# FC_main.net
KiCad netlist of a schematic drawn in Altium Designer
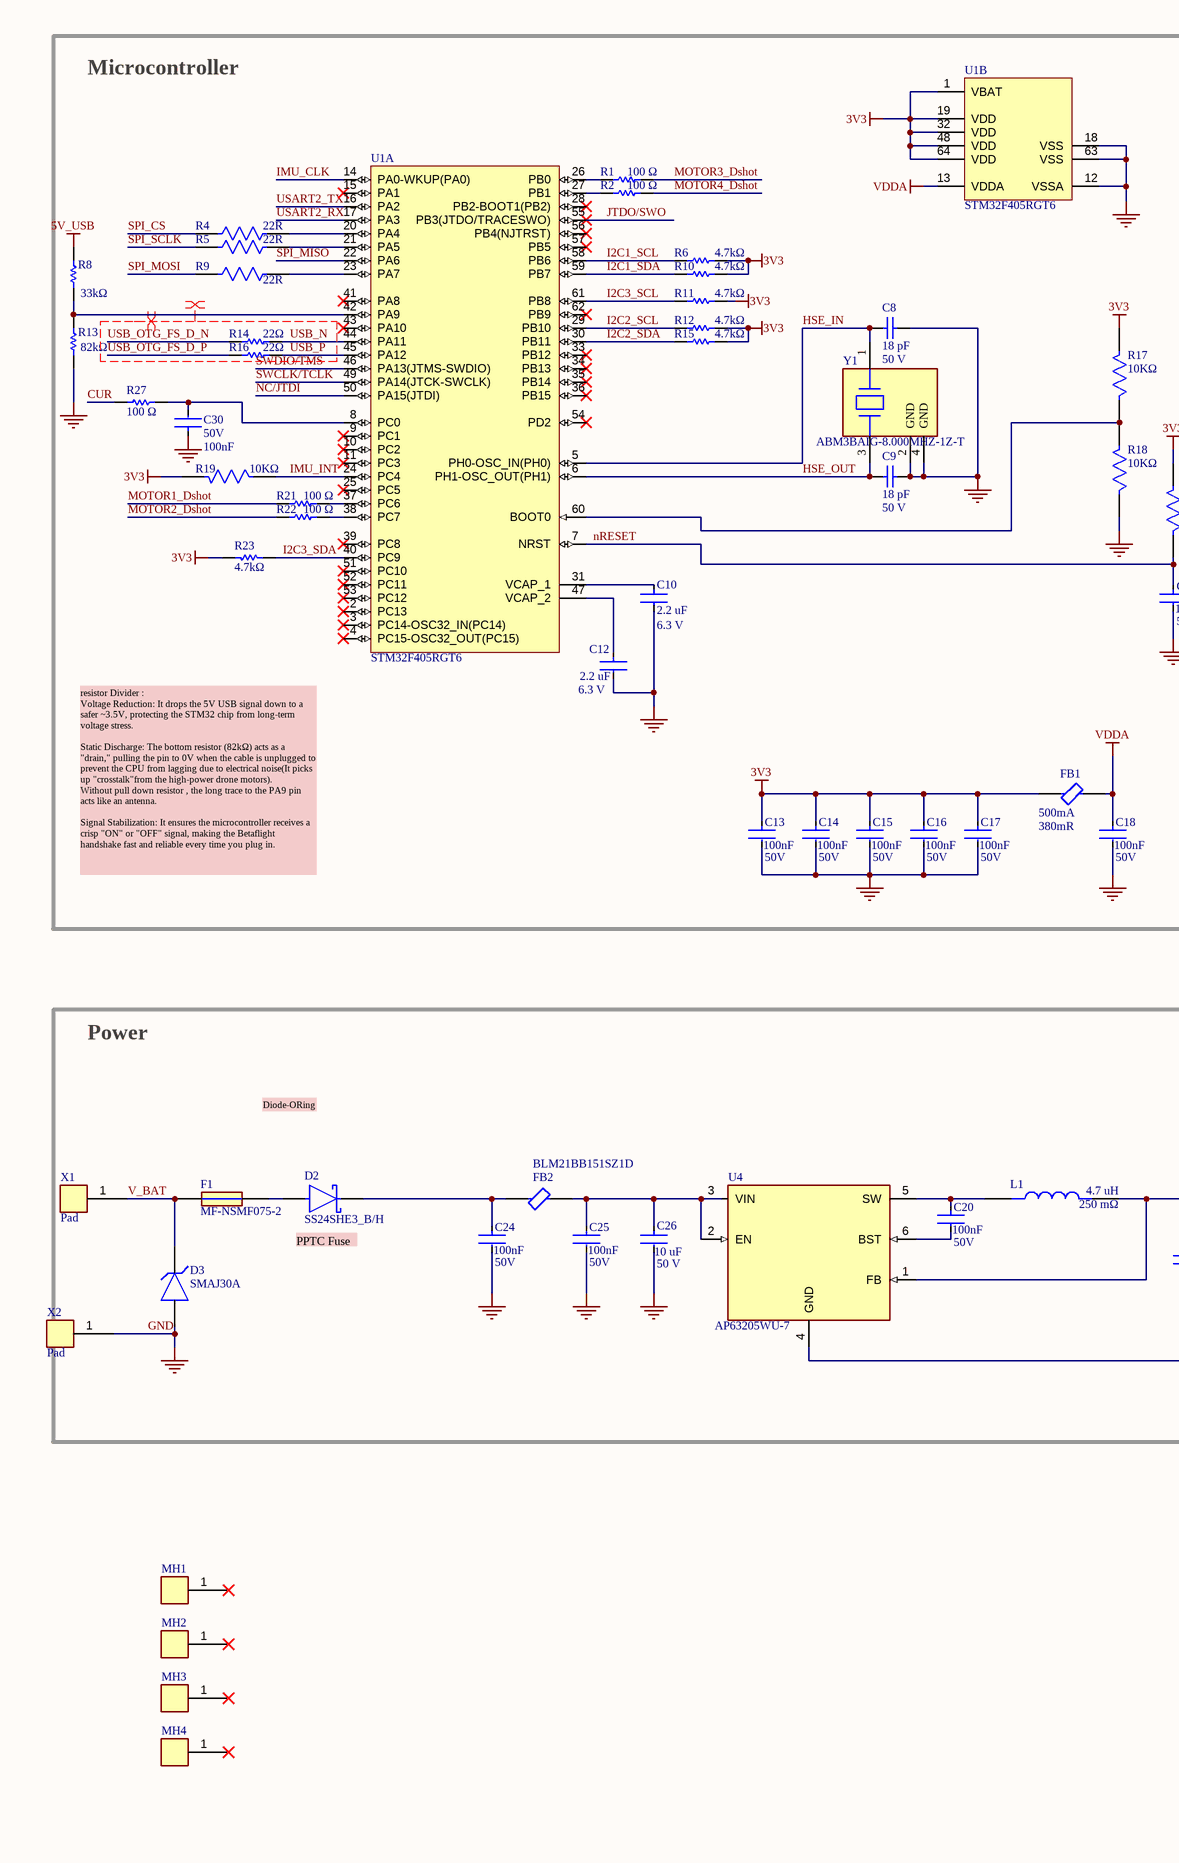
[diagram p0: FC_main.SchDoc, left]
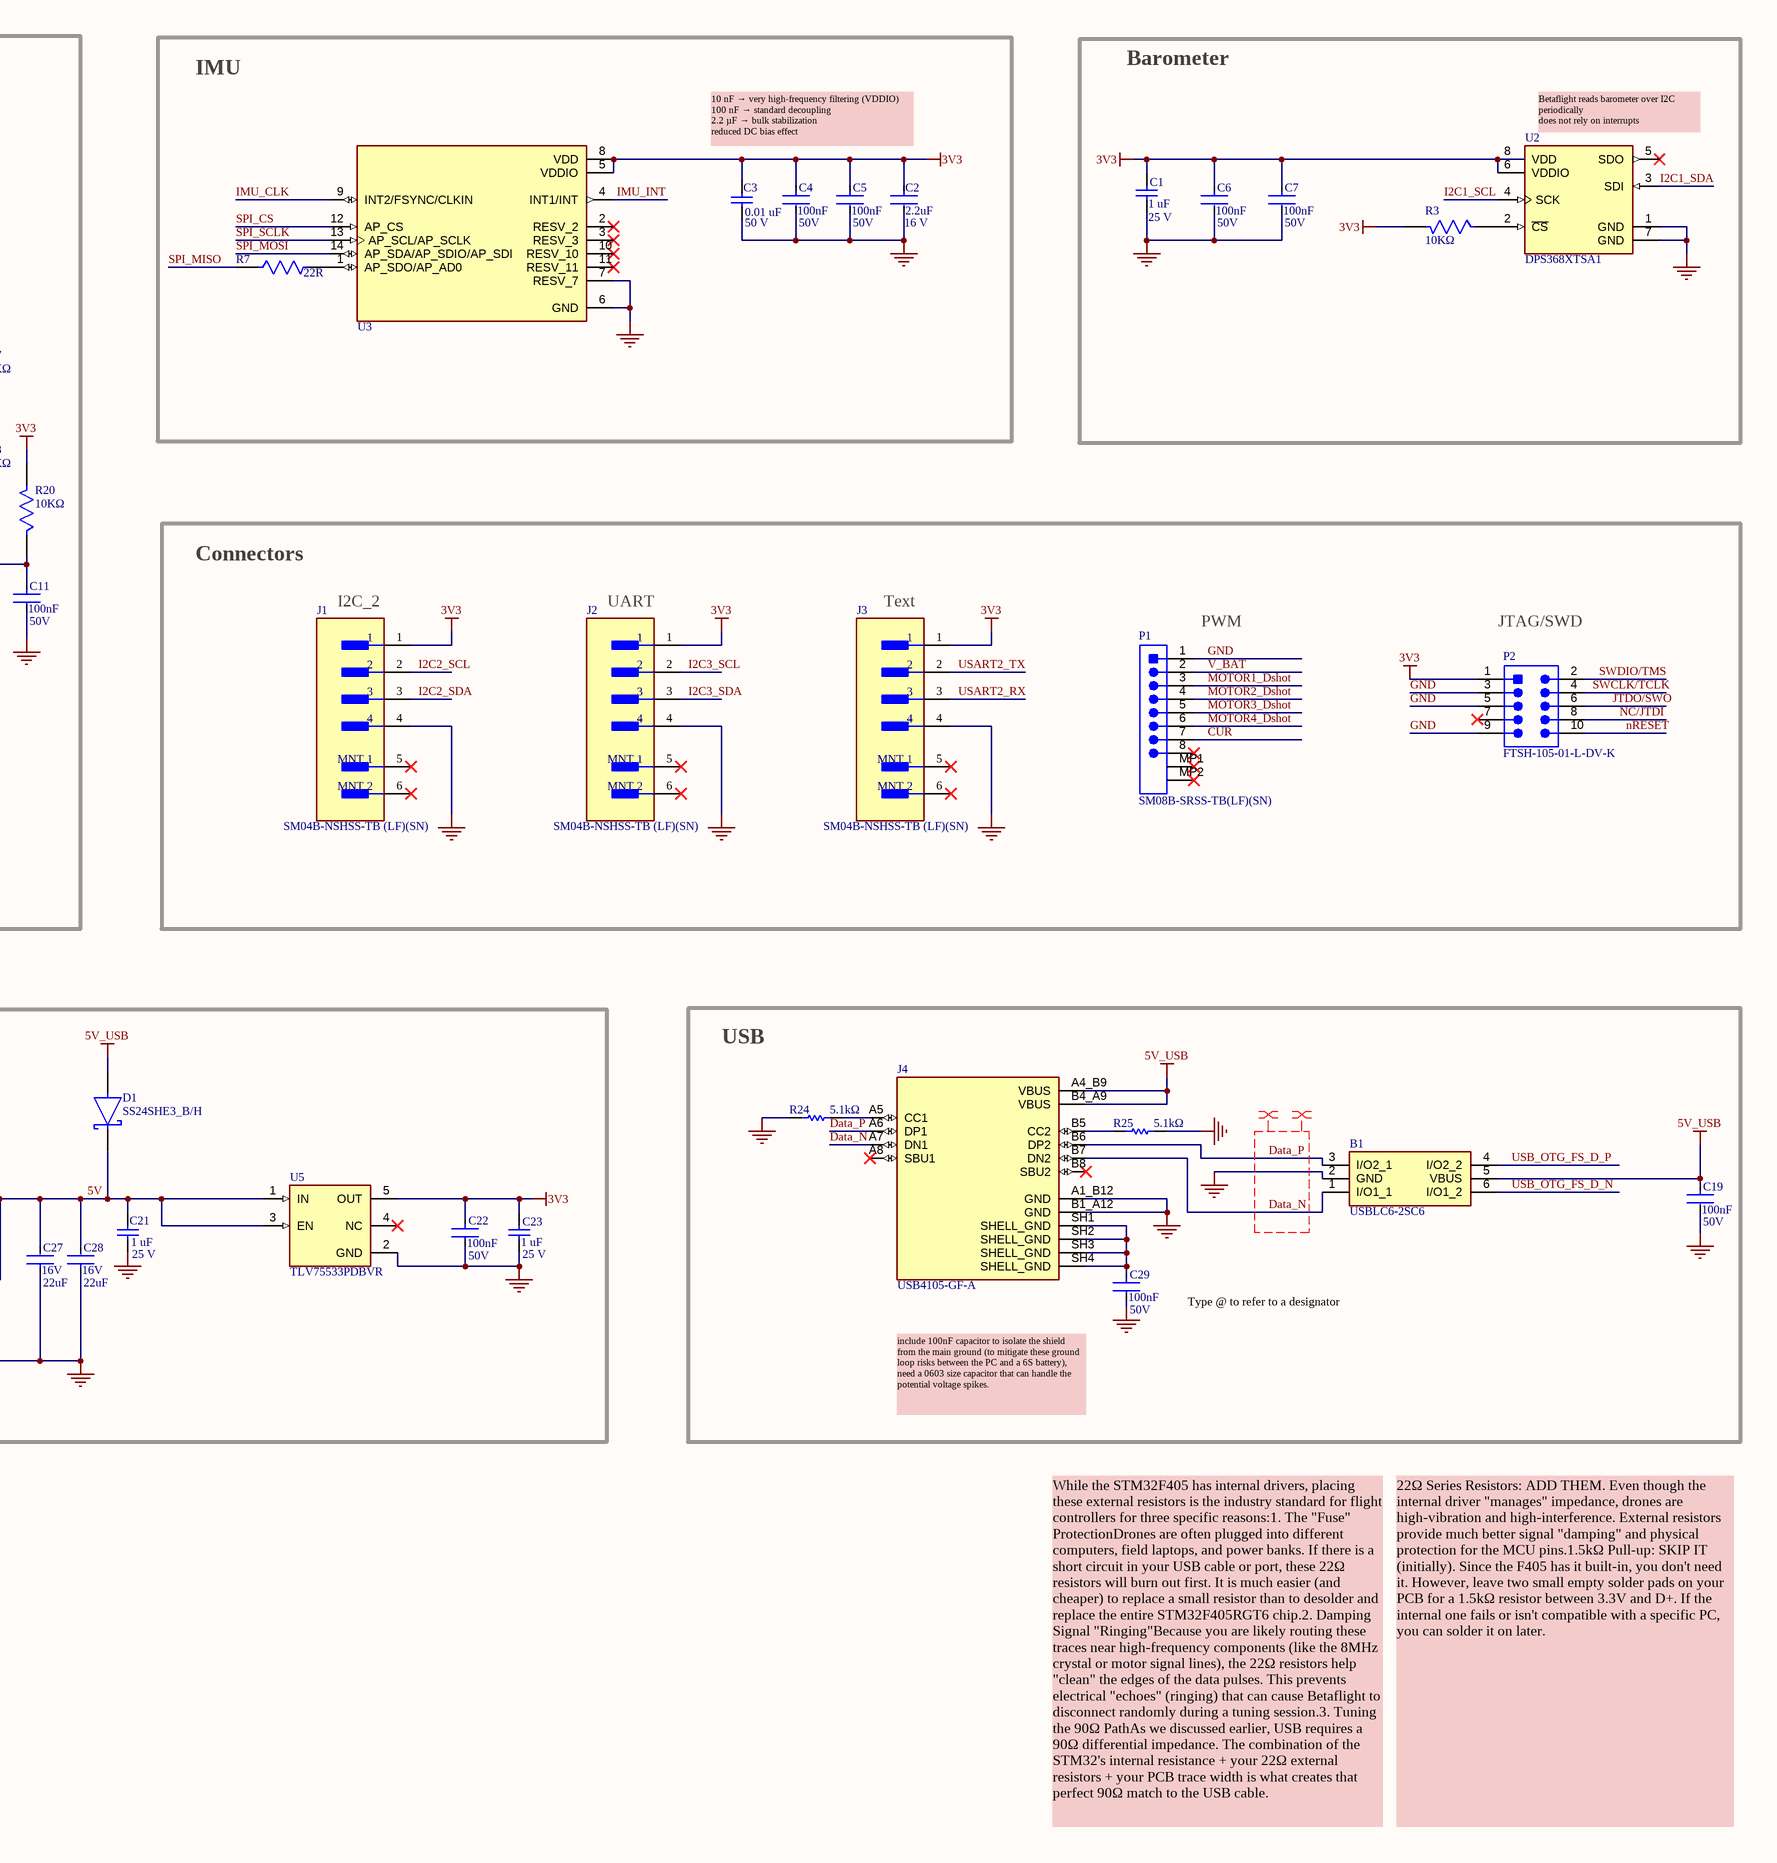
[diagram p1: FC_main.SchDoc, right]

(export (version "E")
  (design (tool "Eeschema 10.0.6"))
  (components
    (comp (ref "B1")
      (value "USBLC6-2SC6")
      (footprint "SOT95P280X145-6N")
      (description "TVS Diode Array Uni-Directional USBLC6-2SC6 17V, SOT-23 6-Pin")
      (fields (field (name "MOUSER PART NUMBER") "511-USBLC6-2SC6"))
      (libsource (lib "USBLC6-2SC6") (part "USBLC6-2SC6"))
    )
    (comp (ref "C1")
      (value "GRM188R71E105KA12D")
      (footprint "CAPC1608X90X35ML10T15")
      (fields
        (field (name "MANUFACTURER") "Murata")
        (field (name "CAPACITANCE") "1 uF")
        (field (name "RATED DC VOLTAGE") "25 V")
      )
      (libsource (lib "Altium Content Vault") (part "CAP"))
    )
    (comp (ref "C2")
      (value "GRM188Z71C225KE43D")
      (footprint "FP-GRM188-0_2-MFG")
      (description "Chip Multilayer Ceramic Capacitors for General Purpose, 0603, 2.2uF, X7R, 15%, 10%, 16V")
      (fields (field (name "CAPACITANCE") "2.2uF") (field (name "RATED VOLTAGE DC") "16 V"))
      (libsource (lib "Altium Content Vault") (part "11868f565c42a9108669ba33697ecf6"))
    )
    (comp (ref "C3")
      (value "GCM188R71H103KA37J")
      (footprint "CAPC1608X90X35NL10T15")
      (fields
        (field (name "MANUFACTURER") "Murata")
        (field (name "CAPACITANCE") "0.01 uF")
        (field (name "RATED DC VOLTAGE") "50 V")
      )
      (libsource (lib "Altium Content Vault") (part "CAP"))
    )
    (comp (ref "C4")
      (value "CGA3E2X7R1H104K080AA")
      (footprint "FP-CGA3E-0_3-0_1-IPC_A")
      (description "Cap Ceramic 100nF 50V X7R 10% Pad SMD 0603 +125°C Automotive T/R")
      (fields
        (field (name "TOLERANCE") "10%")
        (field (name "VOLTAGE RATING") "50V")
        (field (name "CAPACITANCE") "100nF")
        (field (name "VOLTAGE") "50V")
      )
      (libsource (lib "Altium Content Vault") (part "b4654b650e69147ec39a6b967a45e02"))
    )
    (comp (ref "C5")
      (value "CGA3E2X7R1H104K080AA")
      (footprint "FP-CGA3E-0_3-0_1-IPC_A")
      (description "Cap Ceramic 100nF 50V X7R 10% Pad SMD 0603 +125°C Automotive T/R")
      (fields
        (field (name "TOLERANCE") "10%")
        (field (name "VOLTAGE RATING") "50V")
        (field (name "CAPACITANCE") "100nF")
        (field (name "VOLTAGE") "50V")
      )
      (libsource (lib "Altium Content Vault") (part "b4654b650e69147ec39a6b967a45e02"))
    )
    (comp (ref "C6")
      (value "CGA3E2X7R1H104K080AA")
      (footprint "FP-CGA3E-0_3-0_1-IPC_A")
      (description "Cap Ceramic 100nF 50V X7R 10% Pad SMD 0603 +125°C Automotive T/R")
      (fields
        (field (name "TOLERANCE") "10%")
        (field (name "VOLTAGE RATING") "50V")
        (field (name "CAPACITANCE") "100nF")
        (field (name "VOLTAGE") "50V")
      )
      (libsource (lib "Altium Content Vault") (part "b4654b650e69147ec39a6b967a45e02"))
    )
    (comp (ref "C7")
      (value "CGA3E2X7R1H104K080AA")
      (footprint "FP-CGA3E-0_3-0_1-IPC_A")
      (description "Cap Ceramic 100nF 50V X7R 10% Pad SMD 0603 +125°C Automotive T/R")
      (fields
        (field (name "TOLERANCE") "10%")
        (field (name "VOLTAGE RATING") "50V")
        (field (name "CAPACITANCE") "100nF")
        (field (name "VOLTAGE") "50V")
      )
      (libsource (lib "Altium Content Vault") (part "b4654b650e69147ec39a6b967a45e02"))
    )
    (comp (ref "C8")
      (value "GRM1555C1H180JA01D")
      (footprint "CAPC1005X55X25NL05T10")
      (fields
        (field (name "MANUFACTURER") "Murata")
        (field (name "CAPACITANCE") "18 pF")
        (field (name "RATED DC VOLTAGE") "50 V")
      )
      (libsource (lib "Altium Content Vault") (part "CAP"))
    )
    (comp (ref "C9")
      (value "GRM1555C1H180JA01D")
      (footprint "CAPC1005X55X25NL05T10")
      (fields
        (field (name "MANUFACTURER") "Murata")
        (field (name "CAPACITANCE") "18 pF")
        (field (name "RATED DC VOLTAGE") "50 V")
      )
      (libsource (lib "Altium Content Vault") (part "CAP"))
    )
    (comp (ref "C10")
      (value "CC0603KRX7R5BB225")
      (footprint "FP-CC0603-DA-MFG")
      (description "0603 2.2 uF 6.3 V 10% Tolerance X7R Multilayer Ceramic Capacitor")
      (fields
        (field (name "VOLTAGE") "6.3 V")
        (field (name "OCTOPART") "https://octopart.com/cc0603krx7r5bb225-yageo-25629540")
        (field (name "CAPACITANCE") "2.2 uF")
        (field (name "MANUFACTURER") "YAGEO")
      )
      (libsource (lib "Altium Content Vault") (part "11868f565c42a9108669ba33697ecf6"))
    )
    (comp (ref "C11")
      (value "CGA3E2X7R1H104K080AA")
      (footprint "FP-CGA3E-0_3-0_1-IPC_A")
      (description "Cap Ceramic 100nF 50V X7R 10% Pad SMD 0603 +125°C Automotive T/R")
      (fields
        (field (name "TOLERANCE") "10%")
        (field (name "VOLTAGE RATING") "50V")
        (field (name "CAPACITANCE") "100nF")
        (field (name "VOLTAGE") "50V")
      )
      (libsource (lib "Altium Content Vault") (part "b4654b650e69147ec39a6b967a45e02"))
    )
    (comp (ref "C12")
      (value "CC0603KRX7R5BB225")
      (footprint "FP-CC0603-DA-MFG")
      (description "0603 2.2 uF 6.3 V 10% Tolerance X7R Multilayer Ceramic Capacitor")
      (fields
        (field (name "VOLTAGE") "6.3 V")
        (field (name "OCTOPART") "https://octopart.com/cc0603krx7r5bb225-yageo-25629540")
        (field (name "CAPACITANCE") "2.2 uF")
        (field (name "MANUFACTURER") "YAGEO")
      )
      (libsource (lib "Altium Content Vault") (part "11868f565c42a9108669ba33697ecf6"))
    )
    (comp (ref "C13")
      (value "CGA3E2X7R1H104K080AA")
      (footprint "FP-CGA3E-0_3-0_1-IPC_A")
      (description "Cap Ceramic 100nF 50V X7R 10% Pad SMD 0603 +125°C Automotive T/R")
      (fields
        (field (name "TOLERANCE") "10%")
        (field (name "VOLTAGE RATING") "50V")
        (field (name "CAPACITANCE") "100nF")
        (field (name "VOLTAGE") "50V")
      )
      (libsource (lib "Altium Content Vault") (part "b4654b650e69147ec39a6b967a45e02"))
    )
    (comp (ref "C14")
      (value "CGA3E2X7R1H104K080AA")
      (footprint "FP-CGA3E-0_3-0_1-IPC_A")
      (description "Cap Ceramic 100nF 50V X7R 10% Pad SMD 0603 +125°C Automotive T/R")
      (fields
        (field (name "TOLERANCE") "10%")
        (field (name "VOLTAGE RATING") "50V")
        (field (name "CAPACITANCE") "100nF")
        (field (name "VOLTAGE") "50V")
      )
      (libsource (lib "Altium Content Vault") (part "b4654b650e69147ec39a6b967a45e02"))
    )
    (comp (ref "C15")
      (value "CGA3E2X7R1H104K080AA")
      (footprint "FP-CGA3E-0_3-0_1-IPC_A")
      (description "Cap Ceramic 100nF 50V X7R 10% Pad SMD 0603 +125°C Automotive T/R")
      (fields
        (field (name "TOLERANCE") "10%")
        (field (name "VOLTAGE RATING") "50V")
        (field (name "CAPACITANCE") "100nF")
        (field (name "VOLTAGE") "50V")
      )
      (libsource (lib "Altium Content Vault") (part "b4654b650e69147ec39a6b967a45e02"))
    )
    (comp (ref "C16")
      (value "CGA3E2X7R1H104K080AA")
      (footprint "FP-CGA3E-0_3-0_1-IPC_A")
      (description "Cap Ceramic 100nF 50V X7R 10% Pad SMD 0603 +125°C Automotive T/R")
      (fields
        (field (name "TOLERANCE") "10%")
        (field (name "VOLTAGE RATING") "50V")
        (field (name "CAPACITANCE") "100nF")
        (field (name "VOLTAGE") "50V")
      )
      (libsource (lib "Altium Content Vault") (part "b4654b650e69147ec39a6b967a45e02"))
    )
    (comp (ref "C17")
      (value "CGA3E2X7R1H104K080AA")
      (footprint "FP-CGA3E-0_3-0_1-IPC_A")
      (description "Cap Ceramic 100nF 50V X7R 10% Pad SMD 0603 +125°C Automotive T/R")
      (fields
        (field (name "TOLERANCE") "10%")
        (field (name "VOLTAGE RATING") "50V")
        (field (name "CAPACITANCE") "100nF")
        (field (name "VOLTAGE") "50V")
      )
      (libsource (lib "Altium Content Vault") (part "b4654b650e69147ec39a6b967a45e02"))
    )
    (comp (ref "C18")
      (value "CGA3E2X7R1H104K080AA")
      (footprint "FP-CGA3E-0_3-0_1-IPC_A")
      (description "Cap Ceramic 100nF 50V X7R 10% Pad SMD 0603 +125°C Automotive T/R")
      (fields
        (field (name "TOLERANCE") "10%")
        (field (name "VOLTAGE RATING") "50V")
        (field (name "CAPACITANCE") "100nF")
        (field (name "VOLTAGE") "50V")
      )
      (libsource (lib "Altium Content Vault") (part "b4654b650e69147ec39a6b967a45e02"))
    )
    (comp (ref "C19")
      (value "CGA3E2X7R1H104K080AA")
      (footprint "FP-CGA3E-0_3-0_1-IPC_A")
      (description "Cap Ceramic 100nF 50V X7R 10% Pad SMD 0603 +125°C Automotive T/R")
      (fields
        (field (name "TOLERANCE") "10%")
        (field (name "VOLTAGE RATING") "50V")
        (field (name "CAPACITANCE") "100nF")
        (field (name "VOLTAGE") "50V")
      )
      (libsource (lib "Altium Content Vault") (part "b4654b650e69147ec39a6b967a45e02"))
    )
    (comp (ref "C20")
      (value "CGA3E2X7R1H104K080AA")
      (footprint "FP-CGA3E-0_3-0_1-IPC_A")
      (description "Cap Ceramic 100nF 50V X7R 10% Pad SMD 0603 +125°C Automotive T/R")
      (fields
        (field (name "TOLERANCE") "10%")
        (field (name "VOLTAGE RATING") "50V")
        (field (name "CAPACITANCE") "100nF")
        (field (name "VOLTAGE") "50V")
      )
      (libsource (lib "Altium Content Vault") (part "b4654b650e69147ec39a6b967a45e02"))
    )
    (comp (ref "C21")
      (value "GRM188R71E105KA12D")
      (footprint "CAPC1608X90X35ML10T15")
      (fields
        (field (name "MANUFACTURER") "Murata")
        (field (name "CAPACITANCE") "1 uF")
        (field (name "RATED DC VOLTAGE") "25 V")
      )
      (libsource (lib "Altium Content Vault") (part "CAP"))
    )
    (comp (ref "C22")
      (value "CGA3E2X7R1H104K080AA")
      (footprint "FP-CGA3E-0_3-0_1-IPC_A")
      (description "Cap Ceramic 100nF 50V X7R 10% Pad SMD 0603 +125°C Automotive T/R")
      (fields
        (field (name "TOLERANCE") "10%")
        (field (name "VOLTAGE RATING") "50V")
        (field (name "CAPACITANCE") "100nF")
        (field (name "VOLTAGE") "50V")
      )
      (libsource (lib "Altium Content Vault") (part "b4654b650e69147ec39a6b967a45e02"))
    )
    (comp (ref "C23")
      (value "GRM188R71E105KA12D")
      (footprint "CAPC1608X90X35ML10T15")
      (fields
        (field (name "MANUFACTURER") "Murata")
        (field (name "CAPACITANCE") "1 uF")
        (field (name "RATED DC VOLTAGE") "25 V")
      )
      (libsource (lib "Altium Content Vault") (part "CAP"))
    )
    (comp (ref "C24")
      (value "CGA3E2X7R1H104K080AA")
      (footprint "FP-CGA3E-0_3-0_1-IPC_A")
      (description "Cap Ceramic 100nF 50V X7R 10% Pad SMD 0603 +125°C Automotive T/R")
      (fields
        (field (name "TOLERANCE") "10%")
        (field (name "VOLTAGE RATING") "50V")
        (field (name "CAPACITANCE") "100nF")
        (field (name "VOLTAGE") "50V")
      )
      (libsource (lib "Altium Content Vault") (part "b4654b650e69147ec39a6b967a45e02"))
    )
    (comp (ref "C25")
      (value "CGA3E2X7R1H104K080AA")
      (footprint "FP-CGA3E-0_3-0_1-IPC_A")
      (description "Cap Ceramic 100nF 50V X7R 10% Pad SMD 0603 +125°C Automotive T/R")
      (fields
        (field (name "TOLERANCE") "10%")
        (field (name "VOLTAGE RATING") "50V")
        (field (name "CAPACITANCE") "100nF")
        (field (name "VOLTAGE") "50V")
      )
      (libsource (lib "Altium Content Vault") (part "b4654b650e69147ec39a6b967a45e02"))
    )
    (comp (ref "C26")
      (value "C3216X7R1H106K160AC")
      (footprint "FP-C3216-160-0_3-MFG")
      (description "Multilayer Ceramic Capacitors 10uF ±10% 50V X7R SMD 1206")
      (fields (field (name "CAPACITANCE") "10 uF") (field (name "RATED DC VOLTAGE") "50 V"))
      (libsource (lib "Altium Content Vault") (part "02cd4be3c70576c341d710602a673aa"))
    )
    (comp (ref "C27")
      (value "C3225X7R1C226K250AC")
      (footprint "FP-C3225-250-0_4-IPC_C")
      (description "Multilayer Ceramic Capacitors 22uF ±10% 16V X7R SMD 1210")
      (fields
        (field (name "VOLTAGE RATING (DC)") "16V")
        (field (name "VOLTAGE") "16V")
        (field (name "TOLERANCE") "10%")
        (field (name "CAPACITANCE") "22uF")
      )
      (libsource (lib "Altium Content Vault") (part "02cd4be3c70576c341d710602a673aa"))
    )
    (comp (ref "C28")
      (value "C3225X7R1C226K250AC")
      (footprint "FP-C3225-250-0_4-IPC_C")
      (description "Multilayer Ceramic Capacitors 22uF ±10% 16V X7R SMD 1210")
      (fields
        (field (name "VOLTAGE RATING (DC)") "16V")
        (field (name "VOLTAGE") "16V")
        (field (name "TOLERANCE") "10%")
        (field (name "CAPACITANCE") "22uF")
      )
      (libsource (lib "Altium Content Vault") (part "02cd4be3c70576c341d710602a673aa"))
    )
    (comp (ref "C29")
      (value "CGA3E2X7R1H104K080AA")
      (footprint "FP-CGA3E-0_3-0_1-IPC_A")
      (description "Cap Ceramic 100nF 50V X7R 10% Pad SMD 0603 +125°C Automotive T/R")
      (fields
        (field (name "TOLERANCE") "10%")
        (field (name "VOLTAGE RATING") "50V")
        (field (name "CAPACITANCE") "100nF")
        (field (name "VOLTAGE") "50V")
      )
      (libsource (lib "Altium Content Vault") (part "b4654b650e69147ec39a6b967a45e02"))
    )
    (comp (ref "C30")
      (value "CGA3E2X7R1H104K080AA")
      (footprint "FP-CGA3E-0_3-0_1-IPC_A")
      (description "Cap Ceramic 100nF 50V X7R 10% Pad SMD 0603 +125°C Automotive T/R")
      (fields
        (field (name "TOLERANCE") "10%")
        (field (name "VOLTAGE RATING") "50V")
        (field (name "CAPACITANCE") "100nF")
        (field (name "VOLTAGE") "50V")
      )
      (libsource (lib "Altium Content Vault") (part "b4654b650e69147ec39a6b967a45e02"))
    )
    (comp (ref "D1")
      (value "SS24SHE3_B/H")
      (footprint "FP-95400-MFG")
      (description "DIODE SCHOTTKY 2A 40V DO-214AC")
      (libsource (lib "Altium Content Vault") (part "1d6ec82d83fb6aee721767c19dac4b9"))
    )
    (comp (ref "D2")
      (value "SS24SHE3_B/H")
      (footprint "FP-95400-MFG")
      (description "DIODE SCHOTTKY 2A 40V DO-214AC")
      (libsource (lib "Altium Content Vault") (part "1d6ec82d83fb6aee721767c19dac4b9"))
    )
    (comp (ref "D3")
      (value "SMAJ30A")
      (footprint "FP-SMA-MFG")
      (description "TVS DIODE 30V 48.4V SMA")
      (fields
        (field (name "OCTOPART") "https://octopart.com/smaj30a-bourns-12809375")
        (field (name "MANUFACTURER") "Bourns Inc.")
      )
      (libsource (lib "Altium Content Vault") (part "673ecd2ea4d7fb87b4005b0cb348b7d"))
    )
    (comp (ref "F1")
      (value "MF-NSMF075-2")
      (footprint "FUSC3216X70N")
      (description "Fuse, PTC, Resettable, SMD, 1206, 750mA Bourns 0.75A Surface Mount Resettable Fuse, 6 V")
      (fields (field (name "MOUSER PART NUMBER") "652-MF-NSMF075-2"))
      (libsource (lib "MF-NSMF075-2") (part "MF-NSMF075-2"))
    )
    (comp (ref "FB1")
      (value "BLM18AG601SN1D")
      (footprint "FP-BLM18-0_15-t0_8-MFG")
      (description "Chip Ferrite Bead, 0603, 600Ω @ 100MHz, 0.38Ω, 25%, 500mA")
      (fields
        (field (name "MAX DC CURRENT") "500mA")
        (field (name "DC RESISTANCE (DCR)") "380mR")
        (field (name "TOLERANCE") "25%")
      )
      (libsource (lib "Altium Content Vault") (part "5f30dd21d616792df468990f7003faa"))
    )
    (comp (ref "FB2")
      (value "BLM21BB151SZ1D")
      (footprint "FP-BLM21-0_2-t0_85-e0_5-IPC_B")
      (description "Chip Ferrite Bead, 0805, 150Ω @ 100MHz, 0.21Ω, 25%, 600mA")
      (libsource (lib "Altium Content Vault") (part "5f30dd21d616792df468990f7003faa"))
    )
    (comp (ref "J1")
      (value "SM04B-NSHSS-TB (LF)(SN)")
      (footprint "FP-SM04B-NSHSS-TB_LF_SN-MFG")
      (description "CONN HEADER SMD R/A 4POS 1MM")
      (libsource (lib "Altium Content Vault") (part "3b6f738a5616415d78381ad43816e4a"))
    )
    (comp (ref "J2")
      (value "SM04B-NSHSS-TB (LF)(SN)")
      (footprint "FP-SM04B-NSHSS-TB_LF_SN-MFG")
      (description "CONN HEADER SMD R/A 4POS 1MM")
      (libsource (lib "Altium Content Vault") (part "3b6f738a5616415d78381ad43816e4a"))
    )
    (comp (ref "J3")
      (value "SM04B-NSHSS-TB (LF)(SN)")
      (footprint "FP-SM04B-NSHSS-TB_LF_SN-MFG")
      (description "CONN HEADER SMD R/A 4POS 1MM")
      (libsource (lib "Altium Content Vault") (part "3b6f738a5616415d78381ad43816e4a"))
    )
    (comp (ref "J4")
      (value "USB4105-GF-A")
      (footprint "CONN_USB_C_16P_TOP_SMT_TH")
      (libsource (lib "Schlib1") (part "USB4105-GF-A"))
    )
    (comp (ref "L1")
      (value "VLS252010HBX-4R7M-1")
      (footprint "INDC2520X100N")
      (description "4.7uH ±20% Shielded Power Inductor, 1.09A, 2520 (1008 Metric)")
      (fields (field (name "MAXIMUM DC RESISTANCE") "250 mΩ") (field (name "INDUCTANCE") "4.7 uH"))
      (libsource (lib "Schlib1") (part "VLS252010HBX-4R7M-1"))
    )
    (comp (ref "MH1")
      (value "MOUNT_HOLE_M3_GND")
      (footprint "MOUNTING_HOLE_M3")
      (libsource (lib "Schlib1") (part "MOUNT_HOLE_M3_GND"))
    )
    (comp (ref "MH2")
      (value "MOUNT_HOLE_M3_GND")
      (footprint "MOUNTING_HOLE_M3")
      (libsource (lib "Schlib1") (part "MOUNT_HOLE_M3_GND"))
    )
    (comp (ref "MH3")
      (value "MOUNT_HOLE_M3_GND")
      (footprint "MOUNTING_HOLE_M3")
      (libsource (lib "Schlib1") (part "MOUNT_HOLE_M3_GND"))
    )
    (comp (ref "MH4")
      (value "MOUNT_HOLE_M3_GND")
      (footprint "MOUNTING_HOLE_M3")
      (libsource (lib "Schlib1") (part "MOUNT_HOLE_M3_GND"))
    )
    (comp (ref "P1")
      (value "SM08B-SRSS-TB(LF)(SN)")
      (footprint "JST-SM08B-SRSS-TB_V")
      (description "Male Header, Pitch 1 mm, 1 x 8 Position, Height 2.95 mm, -25 to 85 degC, RoHS, Tape and Reel")
      (fields (field (name "MANUFACTURER") "JST"))
      (libsource (lib "Altium Content Vault") (part "CN-1P-2M-R8"))
    )
    (comp (ref "P2")
      (value "FTSH-105-01-L-DV-K")
      (footprint "SMTC-FTSH-105-01-L-DV-K_V")
      (description "Male Header, Pitch 1.27 mm, 2 x 5 Position, Height 6.25 mm")
      (fields (field (name "MANUFACTURER") "Samtec"))
      (libsource (lib "Altium Content Vault") (part "CN-2P-M-R10"))
    )
    (comp (ref "R1")
      (value "RC0402FR-07100RL")
      (footprint "RESC1005X40X25ML05T10")
      (fields (field (name "MANUFACTURER") "Yageo / Phycomp") (field (name "RESISTANCE") "100 Ω"))
      (libsource (lib "Altium Content Vault") (part "RES"))
    )
    (comp (ref "R2")
      (value "RC0402FR-07100RL")
      (footprint "RESC1005X40X25ML05T10")
      (fields (field (name "MANUFACTURER") "Yageo / Phycomp") (field (name "RESISTANCE") "100 Ω"))
      (libsource (lib "Altium Content Vault") (part "RES"))
    )
    (comp (ref "R3")
      (value "10KΩ")
      (footprint "FP-CRGP0603-IPC_C")
      (description "CRGP 0603 10K 1%")
      (fields
        (field (name "OCTOPART") "https://octopart.com/crgp0603f10k-te+connectivity-91018721")
        (field (name "MANUFACTURER PART NUMBER") "CRGP0603F10K")
      )
      (libsource (lib "Altium Content Vault") (part "1029c3af85768c4190bb7ad29bc67b5"))
    )
    (comp (ref "R4")
      (value "RC0603JR-0722RL")
      (footprint "FP-RC0603-0_55-IPC_C")
      (description "RES SMD 22 OHM 5% 1/10W 0603")
      (fields (field (name "TOLERANCE") "5%") (field (name "RESISTANCE") "22R"))
      (libsource (lib "Altium Content Vault") (part "1029c3af85768c4190bb7ad29bc67b5"))
    )
    (comp (ref "R5")
      (value "RC0603JR-0722RL")
      (footprint "FP-RC0603-0_55-IPC_C")
      (description "RES SMD 22 OHM 5% 1/10W 0603")
      (fields (field (name "TOLERANCE") "5%") (field (name "RESISTANCE") "22R"))
      (libsource (lib "Altium Content Vault") (part "1029c3af85768c4190bb7ad29bc67b5"))
    )
    (comp (ref "R6")
      (value "RC0402FR-074K7L")
      (footprint "RESC1005X40X25NL05T10")
      (fields (field (name "MANUFACTURER") "Yageo / Phycomp") (field (name "RESISTANCE") "4.7kΩ"))
      (libsource (lib "Altium Content Vault") (part "RES"))
    )
    (comp (ref "R7")
      (value "RC0603JR-0722RL")
      (footprint "FP-RC0603-0_55-IPC_C")
      (description "RES SMD 22 OHM 5% 1/10W 0603")
      (fields (field (name "TOLERANCE") "5%") (field (name "RESISTANCE") "22R"))
      (libsource (lib "Altium Content Vault") (part "1029c3af85768c4190bb7ad29bc67b5"))
    )
    (comp (ref "R8")
      (value "RC0603FR-0733KL")
      (footprint "RESC1608X55X25LL10T15")
      (description "Chip Resistor, 33 KOhm, +/- 1%, 0.1 W, -55 to 155 degC, 0603 (1608 Metric), RoHS, Tape and Reel")
      (fields
        (field (name "TOLERANCE") "1%")
        (field (name "MANUFACTURER") "Yageo")
        (field (name "RESISTANCE") "33kΩ")
      )
      (libsource (lib "Altium Content Vault") (part "RES-2"))
    )
    (comp (ref "R9")
      (value "RC0603JR-0722RL")
      (footprint "FP-RC0603-0_55-IPC_C")
      (description "RES SMD 22 OHM 5% 1/10W 0603")
      (fields (field (name "TOLERANCE") "5%") (field (name "RESISTANCE") "22R"))
      (libsource (lib "Altium Content Vault") (part "1029c3af85768c4190bb7ad29bc67b5"))
    )
    (comp (ref "R10")
      (value "RC0402FR-074K7L")
      (footprint "RESC1005X40X25NL05T10")
      (fields (field (name "MANUFACTURER") "Yageo / Phycomp") (field (name "RESISTANCE") "4.7kΩ"))
      (libsource (lib "Altium Content Vault") (part "RES"))
    )
    (comp (ref "R11")
      (value "RC0402FR-074K7L")
      (footprint "RESC1005X40X25NL05T10")
      (fields (field (name "MANUFACTURER") "Yageo / Phycomp") (field (name "RESISTANCE") "4.7kΩ"))
      (libsource (lib "Altium Content Vault") (part "RES"))
    )
    (comp (ref "R12")
      (value "RC0402FR-074K7L")
      (footprint "RESC1005X40X25NL05T10")
      (fields (field (name "MANUFACTURER") "Yageo / Phycomp") (field (name "RESISTANCE") "4.7kΩ"))
      (libsource (lib "Altium Content Vault") (part "RES"))
    )
    (comp (ref "R13")
      (value "RC0603FR-0782KL")
      (footprint "RESC1608X55X25LL10T15")
      (description "Chip Resistor, 82 KOhm, +/- 1%, 0.1 W, -55 to 155 degC, 0603 (1608 Metric), RoHS, Tape and Reel")
      (fields
        (field (name "MANUFACTURER") "Yageo")
        (field (name "RESISTANCE") "82kΩ")
        (field (name "TOLERANCE") "1%")
      )
      (libsource (lib "Altium Content Vault") (part "RES-2"))
    )
    (comp (ref "R14")
      (value "RC0603FR-0722RL")
      (footprint "RESC1608X55X25NL10T15")
      (description "Chip Resistor, 22 Ohm, +/- 1%, 0.1 W, -55 to 155 degC, 0603 (1608 Metric), RoHS, Tape and Reel")
      (fields (field (name "RESISTANCE") "22Ω"))
      (libsource (lib "Altium Content Vault") (part "RES-2"))
    )
    (comp (ref "R15")
      (value "RC0402FR-074K7L")
      (footprint "RESC1005X40X25NL05T10")
      (fields (field (name "MANUFACTURER") "Yageo / Phycomp") (field (name "RESISTANCE") "4.7kΩ"))
      (libsource (lib "Altium Content Vault") (part "RES"))
    )
    (comp (ref "R16")
      (value "RC0603FR-0722RL")
      (footprint "RESC1608X55X25NL10T15")
      (description "Chip Resistor, 22 Ohm, +/- 1%, 0.1 W, -55 to 155 degC, 0603 (1608 Metric), RoHS, Tape and Reel")
      (fields (field (name "RESISTANCE") "22Ω"))
      (libsource (lib "Altium Content Vault") (part "RES-2"))
    )
    (comp (ref "R17")
      (value "10KΩ")
      (footprint "FP-CRGP0603-IPC_C")
      (description "CRGP 0603 10K 1%")
      (fields
        (field (name "OCTOPART") "https://octopart.com/crgp0603f10k-te+connectivity-91018721")
        (field (name "MANUFACTURER PART NUMBER") "CRGP0603F10K")
      )
      (libsource (lib "Altium Content Vault") (part "1029c3af85768c4190bb7ad29bc67b5"))
    )
    (comp (ref "R18")
      (value "10KΩ")
      (footprint "FP-CRGP0603-IPC_C")
      (description "CRGP 0603 10K 1%")
      (fields
        (field (name "OCTOPART") "https://octopart.com/crgp0603f10k-te+connectivity-91018721")
        (field (name "MANUFACTURER PART NUMBER") "CRGP0603F10K")
      )
      (libsource (lib "Altium Content Vault") (part "1029c3af85768c4190bb7ad29bc67b5"))
    )
    (comp (ref "R19")
      (value "10KΩ")
      (footprint "FP-CRGP0603-IPC_C")
      (description "CRGP 0603 10K 1%")
      (fields
        (field (name "OCTOPART") "https://octopart.com/crgp0603f10k-te+connectivity-91018721")
        (field (name "MANUFACTURER PART NUMBER") "CRGP0603F10K")
      )
      (libsource (lib "Altium Content Vault") (part "1029c3af85768c4190bb7ad29bc67b5"))
    )
    (comp (ref "R20")
      (value "10KΩ")
      (footprint "FP-CRGP0603-IPC_C")
      (description "CRGP 0603 10K 1%")
      (fields
        (field (name "OCTOPART") "https://octopart.com/crgp0603f10k-te+connectivity-91018721")
        (field (name "MANUFACTURER PART NUMBER") "CRGP0603F10K")
      )
      (libsource (lib "Altium Content Vault") (part "1029c3af85768c4190bb7ad29bc67b5"))
    )
    (comp (ref "R21")
      (value "RC0402FR-07100RL")
      (footprint "RESC1005X40X25ML05T10")
      (fields (field (name "MANUFACTURER") "Yageo / Phycomp") (field (name "RESISTANCE") "100 Ω"))
      (libsource (lib "Altium Content Vault") (part "RES"))
    )
    (comp (ref "R22")
      (value "RC0402FR-07100RL")
      (footprint "RESC1005X40X25ML05T10")
      (fields (field (name "MANUFACTURER") "Yageo / Phycomp") (field (name "RESISTANCE") "100 Ω"))
      (libsource (lib "Altium Content Vault") (part "RES"))
    )
    (comp (ref "R23")
      (value "RC0402FR-074K7L")
      (footprint "RESC1005X40X25NL05T10")
      (fields (field (name "MANUFACTURER") "Yageo / Phycomp") (field (name "RESISTANCE") "4.7kΩ"))
      (libsource (lib "Altium Content Vault") (part "RES"))
    )
    (comp (ref "R24")
      (value "RC0603FR-075K1L")
      (footprint "RESC1608X55X25ML10T15")
      (fields (field (name "MANUFACTURER") "Yageo") (field (name "RESISTANCE") "5.1kΩ"))
      (libsource (lib "Altium Content Vault") (part "RES"))
    )
    (comp (ref "R25")
      (value "RC0603FR-075K1L")
      (footprint "RESC1608X55X25ML10T15")
      (fields (field (name "MANUFACTURER") "Yageo") (field (name "RESISTANCE") "5.1kΩ"))
      (libsource (lib "Altium Content Vault") (part "RES"))
    )
    (comp (ref "R27")
      (value "RC0402FR-07100RL")
      (footprint "RESC1005X40X25ML05T10")
      (fields (field (name "MANUFACTURER") "Yageo / Phycomp") (field (name "RESISTANCE") "100 Ω"))
      (libsource (lib "Altium Content Vault") (part "RES"))
    )
    (comp (ref "U1")
      (value "STM32F405RGT6")
      (footprint "STM-LQFP64_M")
      (fields (field (name "MANUFACTURER") "STMicroelectronics"))
      (libsource (lib "Altium Content Vault") (part "MC-ARM-STM32F4X5-SQ64"))
    )
    (comp (ref "U2")
      (value "DPS368XTSA1")
      (footprint "LGA200P250X200X110-8N")
      (libsource (lib "Schlib1") (part "DPS368XTSA1"))
    )
    (comp (ref "U3")
      (value "ICM-42688-P")
      (footprint "PQFN50P300X250X97-14N")
      (libsource (lib "Schlib1") (part "ICM-42688-P"))
    )
    (comp (ref "U4")
      (value "AP63205WU-7")
      (footprint "SOT95P280X145-6N")
      (libsource (lib "Schlib1") (part "AP63205WU-7"))
    )
    (comp (ref "U5")
      (value "TLV75533PDBVR")
      (footprint "FP-DBV0005A-MFG")
      (description "IC REG LINEAR 3.3V 500MA SOT23-5")
      (fields
        (field (name "MANUFACTURER") "Texas Instruments")
        (field (name "OCTOPART") "https://octopart.com/tlv75533pdbvr-texas+instruments-91272349")
      )
      (libsource (lib "Altium Content Vault") (part "bc27d4aa6bca38f00d7b0ca125c90e0"))
    )
    (comp (ref "X1") (value "Pad") (footprint "Solder_Wire_Pad") (libsource (lib "Schlib1") (part "Pad")))
    (comp (ref "X2") (value "Pad") (footprint "Solder_Wire_Pad") (libsource (lib "Schlib1") (part "Pad")))
    (comp (ref "Y1")
      (value "ABM3BAIG-8.000MHZ-1Z-T")
      (footprint "FP-ABM3BAIG-MFG")
      (description "CRYSTAL 8.0000MHZ 18PF SMD")
      (libsource (lib "Altium Content Vault") (part "3dd7ae69e6a56028198fd7abc02d048"))
    )
  )
  (nets
    (net (code "1") (name "/5V") (class "Default")
      (node (ref "C21") (pin "2") (pinfunction "2_2") (pintype "passive"))
      (node (ref "C27") (pin "2") (pinfunction "2_2") (pintype "passive"))
      (node (ref "C28") (pin "2") (pinfunction "2_2") (pintype "passive"))
      (node (ref "D1") (pin "1") (pinfunction "C_1") (pintype "passive"))
      (node (ref "L1") (pin "2") (pinfunction "2_2") (pintype "passive"))
      (node (ref "U4") (pin "1") (pinfunction "FB_1") (pintype "input"))
      (node (ref "U5") (pin "1") (pinfunction "IN_1") (pintype "input"))
      (node (ref "U5") (pin "3") (pinfunction "EN_3") (pintype "input"))
    )
    (net (code "2") (name "/CUR") (class "Default")
      (node (ref "P1") (pin "7") (pinfunction "7_7") (pintype "passive"))
      (node (ref "R27") (pin "1") (pinfunction "1_1") (pintype "passive"))
    )
    (net (code "3") (name "/Data_N") (class "Default")
      (node (ref "B1") (pin "1") (pinfunction "I/O1_1_1") (pintype "passive"))
      (node (ref "J4") (pin "A7") (pinfunction "DN1_A7") (pintype "bidirectional"))
      (node (ref "J4") (pin "B7") (pinfunction "DN2_B7") (pintype "bidirectional"))
    )
    (net (code "4") (name "/Data_P") (class "Default")
      (node (ref "B1") (pin "3") (pinfunction "I/O2_1_3") (pintype "passive"))
      (node (ref "J4") (pin "A6") (pinfunction "DP1_A6") (pintype "bidirectional"))
      (node (ref "J4") (pin "B6") (pinfunction "DP2_B6") (pintype "bidirectional"))
    )
    (net (code "5") (name "/HSE_IN") (class "Default")
      (node (ref "C8") (pin "2") (pinfunction "2_2") (pintype "passive"))
      (node (ref "U1") (pin "5") (pinfunction "PH0-OSC_IN(PH0)_5") (pintype "bidirectional"))
      (node (ref "Y1") (pin "1") (pinfunction "1_1") (pintype "passive"))
    )
    (net (code "6") (name "/HSE_OUT") (class "Default")
      (node (ref "C9") (pin "2") (pinfunction "2_2") (pintype "passive"))
      (node (ref "U1") (pin "6") (pinfunction "PH1-OSC_OUT(PH1)_6") (pintype "bidirectional"))
      (node (ref "Y1") (pin "3") (pinfunction "3_3") (pintype "passive"))
    )
    (net (code "7") (name "/I2C1_SCL") (class "Default")
      (node (ref "R6") (pin "1") (pinfunction "1_1") (pintype "passive"))
      (node (ref "U1") (pin "58") (pinfunction "PB6_58") (pintype "bidirectional"))
      (node (ref "U2") (pin "4") (pinfunction "SCK_4") (pintype "input"))
    )
    (net (code "8") (name "/I2C1_SDA") (class "Default")
      (node (ref "R10") (pin "1") (pinfunction "1_1") (pintype "passive"))
      (node (ref "U1") (pin "59") (pinfunction "PB7_59") (pintype "bidirectional"))
      (node (ref "U2") (pin "3") (pinfunction "SDI_3") (pintype "input"))
    )
    (net (code "9") (name "/I2C2_SCL") (class "Default")
      (node (ref "J1") (pin "2") (pinfunction "2_2") (pintype "passive"))
      (node (ref "R12") (pin "1") (pinfunction "1_1") (pintype "passive"))
      (node (ref "U1") (pin "29") (pinfunction "PB10_29") (pintype "bidirectional"))
    )
    (net (code "10") (name "/I2C2_SDA") (class "Default")
      (node (ref "J1") (pin "3") (pinfunction "3_3") (pintype "passive"))
      (node (ref "R15") (pin "1") (pinfunction "1_1") (pintype "passive"))
      (node (ref "U1") (pin "30") (pinfunction "PB11_30") (pintype "bidirectional"))
    )
    (net (code "11") (name "/I2C3_SCL") (class "Default")
      (node (ref "J2") (pin "2") (pinfunction "2_2") (pintype "passive"))
      (node (ref "R11") (pin "1") (pinfunction "1_1") (pintype "passive"))
      (node (ref "U1") (pin "61") (pinfunction "PB8_61") (pintype "bidirectional"))
    )
    (net (code "12") (name "/I2C3_SDA") (class "Default")
      (node (ref "J2") (pin "3") (pinfunction "3_3") (pintype "passive"))
      (node (ref "R23") (pin "1") (pinfunction "1_1") (pintype "passive"))
      (node (ref "U1") (pin "40") (pinfunction "PC9_40") (pintype "bidirectional"))
    )
    (net (code "13") (name "/IMU_CLK") (class "Default")
      (node (ref "U1") (pin "14") (pinfunction "PA0-WKUP(PA0)_14") (pintype "bidirectional"))
      (node (ref "U3") (pin "9") (pinfunction "INT2/FSYNC/CLKIN_9") (pintype "bidirectional"))
    )
    (net (code "14") (name "/IMU_INT") (class "Default")
      (node (ref "R19") (pin "1") (pinfunction "1_1") (pintype "passive"))
      (node (ref "U1") (pin "24") (pinfunction "PC4_24") (pintype "bidirectional"))
      (node (ref "U3") (pin "4") (pinfunction "INT1/INT_4") (pintype "output"))
    )
    (net (code "15") (name "/JTDO{slash}SWO") (class "Default")
      (node (ref "P2") (pin "6") (pinfunction "6_6") (pintype "passive"))
      (node (ref "U1") (pin "55") (pinfunction "PB3(JTDO/TRACESWO)_55") (pintype "bidirectional"))
    )
    (net (code "16") (name "/MOTOR1_Dshot") (class "Default")
      (node (ref "P1") (pin "3") (pinfunction "3_3") (pintype "passive"))
      (node (ref "R21") (pin "2") (pinfunction "2_2") (pintype "passive"))
    )
    (net (code "17") (name "/MOTOR2_Dshot") (class "Default")
      (node (ref "P1") (pin "4") (pinfunction "4_4") (pintype "passive"))
      (node (ref "R22") (pin "2") (pinfunction "2_2") (pintype "passive"))
    )
    (net (code "18") (name "/MOTOR3_Dshot") (class "Default")
      (node (ref "P1") (pin "5") (pinfunction "5_5") (pintype "passive"))
      (node (ref "R1") (pin "1") (pinfunction "1_1") (pintype "passive"))
    )
    (net (code "19") (name "/MOTOR4_Dshot") (class "Default")
      (node (ref "P1") (pin "6") (pinfunction "6_6") (pintype "passive"))
      (node (ref "R2") (pin "1") (pinfunction "1_1") (pintype "passive"))
    )
    (net (code "20") (name "/NC{slash}JTDI") (class "Default")
      (node (ref "P2") (pin "8") (pinfunction "8_8") (pintype "passive"))
      (node (ref "U1") (pin "50") (pinfunction "PA15(JTDI)_50") (pintype "bidirectional"))
    )
    (net (code "21") (name "/SPI_CS") (class "Default")
      (node (ref "R4") (pin "1") (pinfunction "1_1") (pintype "passive"))
      (node (ref "U3") (pin "12") (pinfunction "AP_CS_12") (pintype "input"))
    )
    (net (code "22") (name "/SPI_MISO") (class "Default")
      (node (ref "R7") (pin "1") (pinfunction "1_1") (pintype "passive"))
      (node (ref "U1") (pin "22") (pinfunction "PA6_22") (pintype "bidirectional"))
    )
    (net (code "23") (name "/SPI_MOSI") (class "Default")
      (node (ref "R9") (pin "1") (pinfunction "1_1") (pintype "passive"))
      (node (ref "U3") (pin "14") (pinfunction "AP_SDA/AP_SDIO/AP_SDI_14") (pintype "bidirectional"))
    )
    (net (code "24") (name "/SPI_SCLK") (class "Default")
      (node (ref "R5") (pin "1") (pinfunction "1_1") (pintype "passive"))
      (node (ref "U3") (pin "13") (pinfunction "AP_SCL/AP_SCLK_13") (pintype "input"))
    )
    (net (code "25") (name "/SWCLK{slash}TCLK") (class "Default")
      (node (ref "P2") (pin "4") (pinfunction "4_4") (pintype "passive"))
      (node (ref "U1") (pin "49") (pinfunction "PA14(JTCK-SWCLK)_49") (pintype "bidirectional"))
    )
    (net (code "26") (name "/SWDIO{slash}TMS") (class "Default")
      (node (ref "P2") (pin "2") (pinfunction "2_2") (pintype "passive"))
      (node (ref "U1") (pin "46") (pinfunction "PA13(JTMS-SWDIO)_46") (pintype "bidirectional"))
    )
    (net (code "27") (name "/USART2_RX") (class "Default")
      (node (ref "J3") (pin "3") (pinfunction "3_3") (pintype "passive"))
      (node (ref "U1") (pin "17") (pinfunction "PA3_17") (pintype "bidirectional"))
    )
    (net (code "28") (name "/USART2_TX") (class "Default")
      (node (ref "J3") (pin "2") (pinfunction "2_2") (pintype "passive"))
      (node (ref "U1") (pin "16") (pinfunction "PA2_16") (pintype "bidirectional"))
    )
    (net (code "29") (name "/USB_N") (class "Default")
      (node (ref "R14") (pin "1") (pinfunction "1_1") (pintype "passive"))
      (node (ref "U1") (pin "44") (pinfunction "PA11_44") (pintype "bidirectional"))
    )
    (net (code "30") (name "/USB_OTG_FS_D_N") (class "Default")
      (node (ref "B1") (pin "6") (pinfunction "I/O1_2_6") (pintype "passive"))
      (node (ref "R14") (pin "2") (pinfunction "2_2") (pintype "passive"))
    )
    (net (code "31") (name "/USB_OTG_FS_D_P") (class "Default")
      (node (ref "B1") (pin "4") (pinfunction "I/O2_2_4") (pintype "passive"))
      (node (ref "R16") (pin "2") (pinfunction "2_2") (pintype "passive"))
    )
    (net (code "32") (name "/USB_P") (class "Default")
      (node (ref "R16") (pin "1") (pinfunction "1_1") (pintype "passive"))
      (node (ref "U1") (pin "45") (pinfunction "PA12_45") (pintype "bidirectional"))
    )
    (net (code "33") (name "/V_BAT") (class "Default")
      (node (ref "D3") (pin "1") (pinfunction "C_1") (pintype "passive"))
      (node (ref "F1") (pin "1") (pinfunction "1_1") (pintype "passive"))
      (node (ref "P1") (pin "2") (pinfunction "2_2") (pintype "passive"))
      (node (ref "X1") (pin "1") (pinfunction "1_1") (pintype "passive"))
    )
    (net (code "34") (name "/nRESET") (class "Default")
      (node (ref "C11") (pin "1") (pinfunction "1_1") (pintype "passive"))
      (node (ref "P2") (pin "10") (pinfunction "10_10") (pintype "passive"))
      (node (ref "R20") (pin "1") (pinfunction "1_1") (pintype "passive"))
      (node (ref "U1") (pin "7") (pinfunction "NRST_7") (pintype "bidirectional"))
    )
    (net (code "35") (name "3V3") (class "Default")
      (node (ref "C1") (pin "2") (pinfunction "2_2") (pintype "passive"))
      (node (ref "C13") (pin "1") (pinfunction "1_1") (pintype "passive"))
      (node (ref "C14") (pin "1") (pinfunction "1_1") (pintype "passive"))
      (node (ref "C15") (pin "1") (pinfunction "1_1") (pintype "passive"))
      (node (ref "C16") (pin "1") (pinfunction "1_1") (pintype "passive"))
      (node (ref "C17") (pin "1") (pinfunction "1_1") (pintype "passive"))
      (node (ref "C2") (pin "1") (pinfunction "1_1") (pintype "passive"))
      (node (ref "C22") (pin "1") (pinfunction "1_1") (pintype "passive"))
      (node (ref "C23") (pin "2") (pinfunction "2_2") (pintype "passive"))
      (node (ref "C3") (pin "2") (pinfunction "2_2") (pintype "passive"))
      (node (ref "C4") (pin "1") (pinfunction "1_1") (pintype "passive"))
      (node (ref "C5") (pin "1") (pinfunction "1_1") (pintype "passive"))
      (node (ref "C6") (pin "1") (pinfunction "1_1") (pintype "passive"))
      (node (ref "C7") (pin "1") (pinfunction "1_1") (pintype "passive"))
      (node (ref "FB1") (pin "1") (pinfunction "1_1") (pintype "passive"))
      (node (ref "J1") (pin "1") (pinfunction "1_1") (pintype "passive"))
      (node (ref "J2") (pin "1") (pinfunction "1_1") (pintype "passive"))
      (node (ref "J3") (pin "1") (pinfunction "1_1") (pintype "passive"))
      (node (ref "P2") (pin "1") (pinfunction "1_1") (pintype "passive"))
      (node (ref "R10") (pin "2") (pinfunction "2_2") (pintype "passive"))
      (node (ref "R11") (pin "2") (pinfunction "2_2") (pintype "passive"))
      (node (ref "R12") (pin "2") (pinfunction "2_2") (pintype "passive"))
      (node (ref "R15") (pin "2") (pinfunction "2_2") (pintype "passive"))
      (node (ref "R17") (pin "2") (pinfunction "2_2") (pintype "passive"))
      (node (ref "R19") (pin "2") (pinfunction "2_2") (pintype "passive"))
      (node (ref "R20") (pin "2") (pinfunction "2_2") (pintype "passive"))
      (node (ref "R23") (pin "2") (pinfunction "2_2") (pintype "passive"))
      (node (ref "R3") (pin "2") (pinfunction "2_2") (pintype "passive"))
      (node (ref "R6") (pin "2") (pinfunction "2_2") (pintype "passive"))
      (node (ref "U1") (pin "1") (pinfunction "VBAT_1") (pintype "power_in"))
      (node (ref "U1") (pin "19") (pinfunction "VDD_19") (pintype "power_in"))
      (node (ref "U1") (pin "32") (pinfunction "VDD_32") (pintype "power_in"))
      (node (ref "U1") (pin "48") (pinfunction "VDD_48") (pintype "power_in"))
      (node (ref "U1") (pin "64") (pinfunction "VDD_64") (pintype "power_in"))
      (node (ref "U2") (pin "6") (pinfunction "VDDIO_6") (pintype "power_in"))
      (node (ref "U2") (pin "8") (pinfunction "VDD_8") (pintype "power_in"))
      (node (ref "U3") (pin "5") (pinfunction "VDDIO_5") (pintype "power_in"))
      (node (ref "U3") (pin "8") (pinfunction "VDD_8") (pintype "power_in"))
      (node (ref "U5") (pin "5") (pinfunction "OUT_5") (pintype "power_in"))
    )
    (net (code "36") (name "5V_USB") (class "Default")
      (node (ref "B1") (pin "5") (pinfunction "VBUS_5") (pintype "passive"))
      (node (ref "C19") (pin "1") (pinfunction "1_1") (pintype "passive"))
      (node (ref "D1") (pin "2") (pinfunction "A_2") (pintype "passive"))
      (node (ref "J4") (pin "A4_B9") (pinfunction "VBUS_A4_B9") (pintype "power_in"))
      (node (ref "J4") (pin "B4_A9") (pinfunction "VBUS_B4_A9") (pintype "power_in"))
      (node (ref "R8") (pin "2") (pinfunction "2_2") (pintype "passive"))
    )
    (net (code "37") (name "GND") (class "Default")
      (node (ref "B1") (pin "2") (pinfunction "GND_2") (pintype "passive"))
      (node (ref "C1") (pin "1") (pinfunction "1_1") (pintype "passive"))
      (node (ref "C10") (pin "2") (pinfunction "2_2") (pintype "passive"))
      (node (ref "C11") (pin "2") (pinfunction "2_2") (pintype "passive"))
      (node (ref "C12") (pin "2") (pinfunction "2_2") (pintype "passive"))
      (node (ref "C13") (pin "2") (pinfunction "2_2") (pintype "passive"))
      (node (ref "C14") (pin "2") (pinfunction "2_2") (pintype "passive"))
      (node (ref "C15") (pin "2") (pinfunction "2_2") (pintype "passive"))
      (node (ref "C16") (pin "2") (pinfunction "2_2") (pintype "passive"))
      (node (ref "C17") (pin "2") (pinfunction "2_2") (pintype "passive"))
      (node (ref "C18") (pin "2") (pinfunction "2_2") (pintype "passive"))
      (node (ref "C19") (pin "2") (pinfunction "2_2") (pintype "passive"))
      (node (ref "C2") (pin "2") (pinfunction "2_2") (pintype "passive"))
      (node (ref "C21") (pin "1") (pinfunction "1_1") (pintype "passive"))
      (node (ref "C22") (pin "2") (pinfunction "2_2") (pintype "passive"))
      (node (ref "C23") (pin "1") (pinfunction "1_1") (pintype "passive"))
      (node (ref "C24") (pin "2") (pinfunction "2_2") (pintype "passive"))
      (node (ref "C25") (pin "2") (pinfunction "2_2") (pintype "passive"))
      (node (ref "C26") (pin "2") (pinfunction "2_2") (pintype "passive"))
      (node (ref "C27") (pin "1") (pinfunction "1_1") (pintype "passive"))
      (node (ref "C28") (pin "1") (pinfunction "1_1") (pintype "passive"))
      (node (ref "C29") (pin "2") (pinfunction "2_2") (pintype "passive"))
      (node (ref "C3") (pin "1") (pinfunction "1_1") (pintype "passive"))
      (node (ref "C30") (pin "1") (pinfunction "1_1") (pintype "passive"))
      (node (ref "C4") (pin "2") (pinfunction "2_2") (pintype "passive"))
      (node (ref "C5") (pin "2") (pinfunction "2_2") (pintype "passive"))
      (node (ref "C6") (pin "2") (pinfunction "2_2") (pintype "passive"))
      (node (ref "C7") (pin "2") (pinfunction "2_2") (pintype "passive"))
      (node (ref "C8") (pin "1") (pinfunction "1_1") (pintype "passive"))
      (node (ref "C9") (pin "1") (pinfunction "1_1") (pintype "passive"))
      (node (ref "D3") (pin "2") (pinfunction "A_2") (pintype "passive"))
      (node (ref "J1") (pin "4") (pinfunction "4_4") (pintype "passive"))
      (node (ref "J2") (pin "4") (pinfunction "4_4") (pintype "passive"))
      (node (ref "J3") (pin "4") (pinfunction "4_4") (pintype "passive"))
      (node (ref "J4") (pin "A1_B12") (pinfunction "GND_A1_B12") (pintype "power_in"))
      (node (ref "J4") (pin "B1_A12") (pinfunction "GND_B1_A12") (pintype "power_in"))
      (node (ref "P1") (pin "1") (pinfunction "1_1") (pintype "passive"))
      (node (ref "P2") (pin "3") (pinfunction "3_3") (pintype "passive"))
      (node (ref "P2") (pin "5") (pinfunction "5_5") (pintype "passive"))
      (node (ref "P2") (pin "9") (pinfunction "9_9") (pintype "passive"))
      (node (ref "R13") (pin "1") (pinfunction "1_1") (pintype "passive"))
      (node (ref "R18") (pin "1") (pinfunction "1_1") (pintype "passive"))
      (node (ref "R24") (pin "1") (pinfunction "1_1") (pintype "passive"))
      (node (ref "R25") (pin "2") (pinfunction "2_2") (pintype "passive"))
      (node (ref "U1") (pin "12") (pinfunction "VSSA_12") (pintype "power_in"))
      (node (ref "U1") (pin "18") (pinfunction "VSS_18") (pintype "power_in"))
      (node (ref "U1") (pin "63") (pinfunction "VSS_63") (pintype "power_in"))
      (node (ref "U2") (pin "1") (pinfunction "GND_1") (pintype "power_in"))
      (node (ref "U2") (pin "7") (pinfunction "GND_7") (pintype "power_in"))
      (node (ref "U3") (pin "6") (pinfunction "GND_6") (pintype "power_in"))
      (node (ref "U3") (pin "7") (pinfunction "RESV_7_7") (pintype "passive"))
      (node (ref "U4") (pin "4") (pinfunction "GND_4") (pintype "power_in"))
      (node (ref "U5") (pin "2") (pinfunction "GND_2") (pintype "power_in"))
      (node (ref "X2") (pin "1") (pinfunction "1_1") (pintype "passive"))
      (node (ref "Y1") (pin "2") (pinfunction "GND_2") (pintype "power_in"))
      (node (ref "Y1") (pin "4") (pinfunction "GND_4") (pintype "power_in"))
    )
    (net (code "38") (name "Net-(C29-Pad1)") (class "Default")
      (node (ref "C29") (pin "1") (pinfunction "1_1") (pintype "passive"))
      (node (ref "J4") (pin "SH1") (pinfunction "SHELL_GND_SH1") (pintype "power_in"))
      (node (ref "J4") (pin "SH2") (pinfunction "SHELL_GND_SH2") (pintype "power_in"))
      (node (ref "J4") (pin "SH3") (pinfunction "SHELL_GND_SH3") (pintype "power_in"))
      (node (ref "J4") (pin "SH4") (pinfunction "SHELL_GND_SH4") (pintype "power_in"))
    )
    (net (code "39") (name "Net-(D2-A)") (class "Default")
      (node (ref "D2") (pin "2") (pinfunction "A_2") (pintype "passive"))
      (node (ref "F1") (pin "2") (pinfunction "2_2") (pintype "passive"))
    )
    (net (code "40") (name "Net-(D2-C)") (class "Default")
      (node (ref "C24") (pin "1") (pinfunction "1_1") (pintype "passive"))
      (node (ref "D2") (pin "1") (pinfunction "C_1") (pintype "passive"))
      (node (ref "FB2") (pin "1") (pinfunction "1_1") (pintype "passive"))
    )
    (net (code "41") (name "Net-(J4-CC1)") (class "Default")
      (node (ref "J4") (pin "A5") (pinfunction "CC1_A5") (pintype "bidirectional"))
      (node (ref "R24") (pin "2") (pinfunction "2_2") (pintype "passive"))
    )
    (net (code "42") (name "Net-(J4-CC2)") (class "Default")
      (node (ref "J4") (pin "B5") (pinfunction "CC2_B5") (pintype "bidirectional"))
      (node (ref "R25") (pin "1") (pinfunction "1_1") (pintype "passive"))
    )
    (net (code "43") (name "Net-(U1A-BOOT0)") (class "Default")
      (node (ref "R17") (pin "1") (pinfunction "1_1") (pintype "passive"))
      (node (ref "R18") (pin "2") (pinfunction "2_2") (pintype "passive"))
      (node (ref "U1") (pin "60") (pinfunction "BOOT0_60") (pintype "input"))
    )
    (net (code "44") (name "Net-(U1A-PA4)") (class "Default")
      (node (ref "R4") (pin "2") (pinfunction "2_2") (pintype "passive"))
      (node (ref "U1") (pin "20") (pinfunction "PA4_20") (pintype "bidirectional"))
    )
    (net (code "45") (name "Net-(U1A-PA5)") (class "Default")
      (node (ref "R5") (pin "2") (pinfunction "2_2") (pintype "passive"))
      (node (ref "U1") (pin "21") (pinfunction "PA5_21") (pintype "bidirectional"))
    )
    (net (code "46") (name "Net-(U1A-PA7)") (class "Default")
      (node (ref "R9") (pin "2") (pinfunction "2_2") (pintype "passive"))
      (node (ref "U1") (pin "23") (pinfunction "PA7_23") (pintype "bidirectional"))
    )
    (net (code "47") (name "Net-(U1A-PA9)") (class "Default")
      (node (ref "R13") (pin "2") (pinfunction "2_2") (pintype "passive"))
      (node (ref "R8") (pin "1") (pinfunction "1_1") (pintype "passive"))
      (node (ref "U1") (pin "42") (pinfunction "PA9_42") (pintype "bidirectional"))
    )
    (net (code "48") (name "Net-(U1A-PB0)") (class "Default")
      (node (ref "R1") (pin "2") (pinfunction "2_2") (pintype "passive"))
      (node (ref "U1") (pin "26") (pinfunction "PB0_26") (pintype "bidirectional"))
    )
    (net (code "49") (name "Net-(U1A-PB1)") (class "Default")
      (node (ref "R2") (pin "2") (pinfunction "2_2") (pintype "passive"))
      (node (ref "U1") (pin "27") (pinfunction "PB1_27") (pintype "bidirectional"))
    )
    (net (code "50") (name "Net-(U1A-PC0)") (class "Default")
      (node (ref "C30") (pin "2") (pinfunction "2_2") (pintype "passive"))
      (node (ref "R27") (pin "2") (pinfunction "2_2") (pintype "passive"))
      (node (ref "U1") (pin "8") (pinfunction "PC0_8") (pintype "bidirectional"))
    )
    (net (code "51") (name "Net-(U1A-PC6)") (class "Default")
      (node (ref "R21") (pin "1") (pinfunction "1_1") (pintype "passive"))
      (node (ref "U1") (pin "37") (pinfunction "PC6_37") (pintype "bidirectional"))
    )
    (net (code "52") (name "Net-(U1A-PC7)") (class "Default")
      (node (ref "R22") (pin "1") (pinfunction "1_1") (pintype "passive"))
      (node (ref "U1") (pin "38") (pinfunction "PC7_38") (pintype "bidirectional"))
    )
    (net (code "53") (name "Net-(U1A-VCAP_1)") (class "Default")
      (node (ref "C10") (pin "1") (pinfunction "1_1") (pintype "passive"))
      (node (ref "U1") (pin "31") (pinfunction "VCAP_1_31") (pintype "power_in"))
    )
    (net (code "54") (name "Net-(U1A-VCAP_2)") (class "Default")
      (node (ref "C12") (pin "1") (pinfunction "1_1") (pintype "passive"))
      (node (ref "U1") (pin "47") (pinfunction "VCAP_2_47") (pintype "power_in"))
    )
    (net (code "55") (name "Net-(U2-~{CS})") (class "Default")
      (node (ref "R3") (pin "1") (pinfunction "1_1") (pintype "passive"))
      (node (ref "U2") (pin "2") (pinfunction "~{CS}_2") (pintype "input"))
    )
    (net (code "56") (name "Net-(U3-AP_SDO{slash}AP_AD0)") (class "Default")
      (node (ref "R7") (pin "2") (pinfunction "2_2") (pintype "passive"))
      (node (ref "U3") (pin "1") (pinfunction "AP_SDO/AP_AD0_1") (pintype "bidirectional"))
    )
    (net (code "57") (name "Net-(U4-BST)") (class "Default")
      (node (ref "C20") (pin "2") (pinfunction "2_2") (pintype "passive"))
      (node (ref "U4") (pin "6") (pinfunction "BST_6") (pintype "input"))
    )
    (net (code "58") (name "Net-(U4-EN)") (class "Default")
      (node (ref "C25") (pin "1") (pinfunction "1_1") (pintype "passive"))
      (node (ref "C26") (pin "1") (pinfunction "1_1") (pintype "passive"))
      (node (ref "FB2") (pin "2") (pinfunction "2_2") (pintype "passive"))
      (node (ref "U4") (pin "2") (pinfunction "EN_2") (pintype "input"))
      (node (ref "U4") (pin "3") (pinfunction "VIN_3") (pintype "power_in"))
    )
    (net (code "59") (name "Net-(U4-SW)") (class "Default")
      (node (ref "C20") (pin "1") (pinfunction "1_1") (pintype "passive"))
      (node (ref "L1") (pin "1") (pinfunction "1_1") (pintype "passive"))
      (node (ref "U4") (pin "5") (pinfunction "SW_5") (pintype "power_in"))
    )
    (net (code "60") (name "VDDA") (class "Default")
      (node (ref "C18") (pin "1") (pinfunction "1_1") (pintype "passive"))
      (node (ref "FB1") (pin "2") (pinfunction "2_2") (pintype "passive"))
      (node (ref "U1") (pin "13") (pinfunction "VDDA_13") (pintype "power_in"))
    )
    (net (code "61") (name "unconnected-(J1-MNT_1-Pad5)") (class "Default")
      (node (ref "J1") (pin "5") (pinfunction "MNT_1_5") (pintype "passive+no_connect"))
    )
    (net (code "62") (name "unconnected-(J1-MNT_2-Pad6)") (class "Default")
      (node (ref "J1") (pin "6") (pinfunction "MNT_2_6") (pintype "passive+no_connect"))
    )
    (net (code "63") (name "unconnected-(J2-MNT_1-Pad5)") (class "Default")
      (node (ref "J2") (pin "5") (pinfunction "MNT_1_5") (pintype "passive+no_connect"))
    )
    (net (code "64") (name "unconnected-(J2-MNT_2-Pad6)") (class "Default")
      (node (ref "J2") (pin "6") (pinfunction "MNT_2_6") (pintype "passive+no_connect"))
    )
    (net (code "65") (name "unconnected-(J3-MNT_1-Pad5)") (class "Default")
      (node (ref "J3") (pin "5") (pinfunction "MNT_1_5") (pintype "passive+no_connect"))
    )
    (net (code "66") (name "unconnected-(J3-MNT_2-Pad6)") (class "Default")
      (node (ref "J3") (pin "6") (pinfunction "MNT_2_6") (pintype "passive+no_connect"))
    )
    (net (code "67") (name "unconnected-(J4-SBU1-PadA8)") (class "Default")
      (node (ref "J4") (pin "A8") (pinfunction "SBU1_A8") (pintype "bidirectional+no_connect"))
    )
    (net (code "68") (name "unconnected-(J4-SBU2-PadB8)") (class "Default")
      (node (ref "J4") (pin "B8") (pinfunction "SBU2_B8") (pintype "bidirectional+no_connect"))
    )
    (net (code "69") (name "unconnected-(MH1-Pad1)") (class "Default")
      (node (ref "MH1") (pin "1") (pinfunction "1_1") (pintype "passive+no_connect"))
    )
    (net (code "70") (name "unconnected-(MH2-Pad1)") (class "Default")
      (node (ref "MH2") (pin "1") (pinfunction "1_1") (pintype "passive+no_connect"))
    )
    (net (code "71") (name "unconnected-(MH3-Pad1)") (class "Default")
      (node (ref "MH3") (pin "1") (pinfunction "1_1") (pintype "passive+no_connect"))
    )
    (net (code "72") (name "unconnected-(MH4-Pad1)") (class "Default")
      (node (ref "MH4") (pin "1") (pinfunction "1_1") (pintype "passive+no_connect"))
    )
    (net (code "73") (name "unconnected-(P1-Pad8)") (class "Default")
      (node (ref "P1") (pin "8") (pinfunction "8_8") (pintype "passive+no_connect"))
    )
    (net (code "74") (name "unconnected-(P1-PadMP1)") (class "Default")
      (node (ref "P1") (pin "MP1") (pinfunction "MP1_MP1") (pintype "passive+no_connect"))
    )
    (net (code "75") (name "unconnected-(P1-PadMP2)") (class "Default")
      (node (ref "P1") (pin "MP2") (pinfunction "MP2_MP2") (pintype "passive+no_connect"))
    )
    (net (code "76") (name "unconnected-(P2-Pad7)") (class "Default")
      (node (ref "P2") (pin "7") (pinfunction "7_7") (pintype "passive+no_connect"))
    )
    (net (code "77") (name "unconnected-(U1A-PA1-Pad15)") (class "Default")
      (node (ref "U1") (pin "15") (pinfunction "PA1_15") (pintype "bidirectional+no_connect"))
    )
    (net (code "78") (name "unconnected-(U1A-PA8-Pad41)") (class "Default")
      (node (ref "U1") (pin "41") (pinfunction "PA8_41") (pintype "bidirectional+no_connect"))
    )
    (net (code "79") (name "unconnected-(U1A-PA10-Pad43)") (class "Default")
      (node (ref "U1") (pin "43") (pinfunction "PA10_43") (pintype "bidirectional+no_connect"))
    )
    (net (code "80") (name "unconnected-(U1A-PB2-BOOT1(PB2)-Pad28)") (class "Default")
      (node (ref "U1") (pin "28") (pinfunction "PB2-BOOT1(PB2)_28") (pintype "bidirectional+no_connect"))
    )
    (net (code "81") (name "unconnected-(U1A-PB4(NJTRST)-Pad56)") (class "Default")
      (node (ref "U1") (pin "56") (pinfunction "PB4(NJTRST)_56") (pintype "bidirectional+no_connect"))
    )
    (net (code "82") (name "unconnected-(U1A-PB5-Pad57)") (class "Default")
      (node (ref "U1") (pin "57") (pinfunction "PB5_57") (pintype "bidirectional+no_connect"))
    )
    (net (code "83") (name "unconnected-(U1A-PB9-Pad62)") (class "Default")
      (node (ref "U1") (pin "62") (pinfunction "PB9_62") (pintype "bidirectional+no_connect"))
    )
    (net (code "84") (name "unconnected-(U1A-PB12-Pad33)") (class "Default")
      (node (ref "U1") (pin "33") (pinfunction "PB12_33") (pintype "bidirectional+no_connect"))
    )
    (net (code "85") (name "unconnected-(U1A-PB13-Pad34)") (class "Default")
      (node (ref "U1") (pin "34") (pinfunction "PB13_34") (pintype "bidirectional+no_connect"))
    )
    (net (code "86") (name "unconnected-(U1A-PB14-Pad35)") (class "Default")
      (node (ref "U1") (pin "35") (pinfunction "PB14_35") (pintype "bidirectional+no_connect"))
    )
    (net (code "87") (name "unconnected-(U1A-PB15-Pad36)") (class "Default")
      (node (ref "U1") (pin "36") (pinfunction "PB15_36") (pintype "bidirectional+no_connect"))
    )
    (net (code "88") (name "unconnected-(U1A-PC1-Pad9)") (class "Default")
      (node (ref "U1") (pin "9") (pinfunction "PC1_9") (pintype "bidirectional+no_connect"))
    )
    (net (code "89") (name "unconnected-(U1A-PC2-Pad10)") (class "Default")
      (node (ref "U1") (pin "10") (pinfunction "PC2_10") (pintype "bidirectional+no_connect"))
    )
    (net (code "90") (name "unconnected-(U1A-PC3-Pad11)") (class "Default")
      (node (ref "U1") (pin "11") (pinfunction "PC3_11") (pintype "bidirectional+no_connect"))
    )
    (net (code "91") (name "unconnected-(U1A-PC5-Pad25)") (class "Default")
      (node (ref "U1") (pin "25") (pinfunction "PC5_25") (pintype "bidirectional+no_connect"))
    )
    (net (code "92") (name "unconnected-(U1A-PC8-Pad39)") (class "Default")
      (node (ref "U1") (pin "39") (pinfunction "PC8_39") (pintype "bidirectional+no_connect"))
    )
    (net (code "93") (name "unconnected-(U1A-PC10-Pad51)") (class "Default")
      (node (ref "U1") (pin "51") (pinfunction "PC10_51") (pintype "bidirectional+no_connect"))
    )
    (net (code "94") (name "unconnected-(U1A-PC11-Pad52)") (class "Default")
      (node (ref "U1") (pin "52") (pinfunction "PC11_52") (pintype "bidirectional+no_connect"))
    )
    (net (code "95") (name "unconnected-(U1A-PC12-Pad53)") (class "Default")
      (node (ref "U1") (pin "53") (pinfunction "PC12_53") (pintype "bidirectional+no_connect"))
    )
    (net (code "96") (name "unconnected-(U1A-PC13-Pad2)") (class "Default")
      (node (ref "U1") (pin "2") (pinfunction "PC13_2") (pintype "bidirectional+no_connect"))
    )
    (net (code "97") (name "unconnected-(U1A-PC14-OSC32_IN(PC14)-Pad3)") (class "Default")
      (node (ref "U1") (pin "3") (pinfunction "PC14-OSC32_IN(PC14)_3") (pintype "bidirectional+no_connect"))
    )
    (net (code "98") (name "unconnected-(U1A-PC15-OSC32_OUT(PC15)-Pad4)") (class "Default")
      (node (ref "U1") (pin "4") (pinfunction "PC15-OSC32_OUT(PC15)_4") (pintype "bidirectional+no_connect"))
    )
    (net (code "99") (name "unconnected-(U1A-PD2-Pad54)") (class "Default")
      (node (ref "U1") (pin "54") (pinfunction "PD2_54") (pintype "bidirectional+no_connect"))
    )
    (net (code "100") (name "unconnected-(U2-SDO-Pad5)") (class "Default")
      (node (ref "U2") (pin "5") (pinfunction "SDO_5") (pintype "output+no_connect"))
    )
    (net (code "101") (name "unconnected-(U3-RESV_2-Pad2)") (class "Default")
      (node (ref "U3") (pin "2") (pinfunction "RESV_2_2") (pintype "passive+no_connect"))
    )
    (net (code "102") (name "unconnected-(U3-RESV_3-Pad3)") (class "Default")
      (node (ref "U3") (pin "3") (pinfunction "RESV_3_3") (pintype "passive+no_connect"))
    )
    (net (code "103") (name "unconnected-(U3-RESV_10-Pad10)") (class "Default")
      (node (ref "U3") (pin "10") (pinfunction "RESV_10_10") (pintype "passive+no_connect"))
    )
    (net (code "104") (name "unconnected-(U3-RESV_11-Pad11)") (class "Default")
      (node (ref "U3") (pin "11") (pinfunction "RESV_11_11") (pintype "passive+no_connect"))
    )
    (net (code "105") (name "unconnected-(U5-NC-Pad4)") (class "Default")
      (node (ref "U5") (pin "4") (pinfunction "NC_4") (pintype "passive+no_connect"))
    )
  )
)
